# Microcontroller.net
KiCad netlist of a schematic drawn in Altium Designer
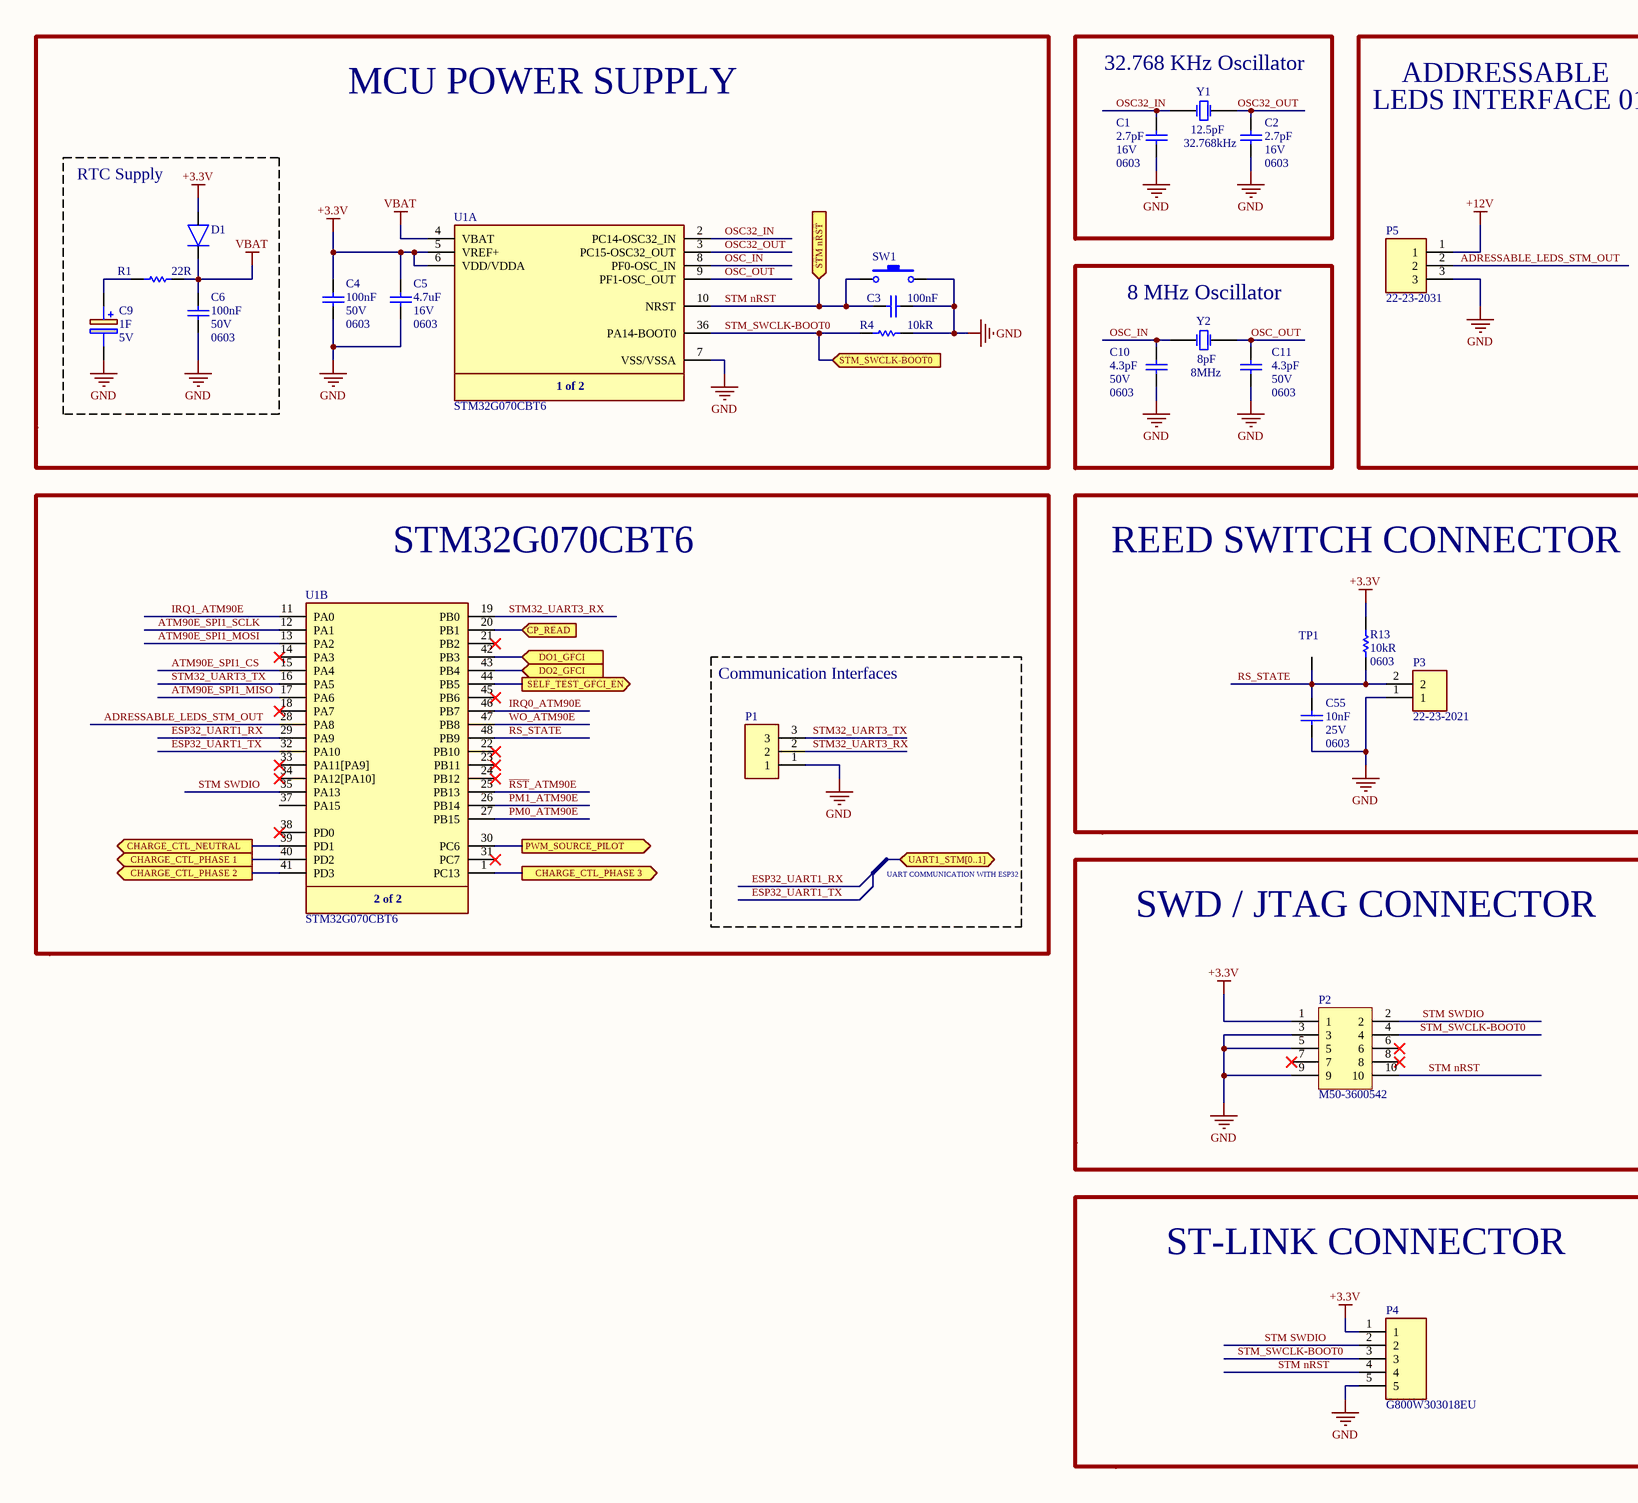
[diagram p0: Microcontroller.SchDoc, left]
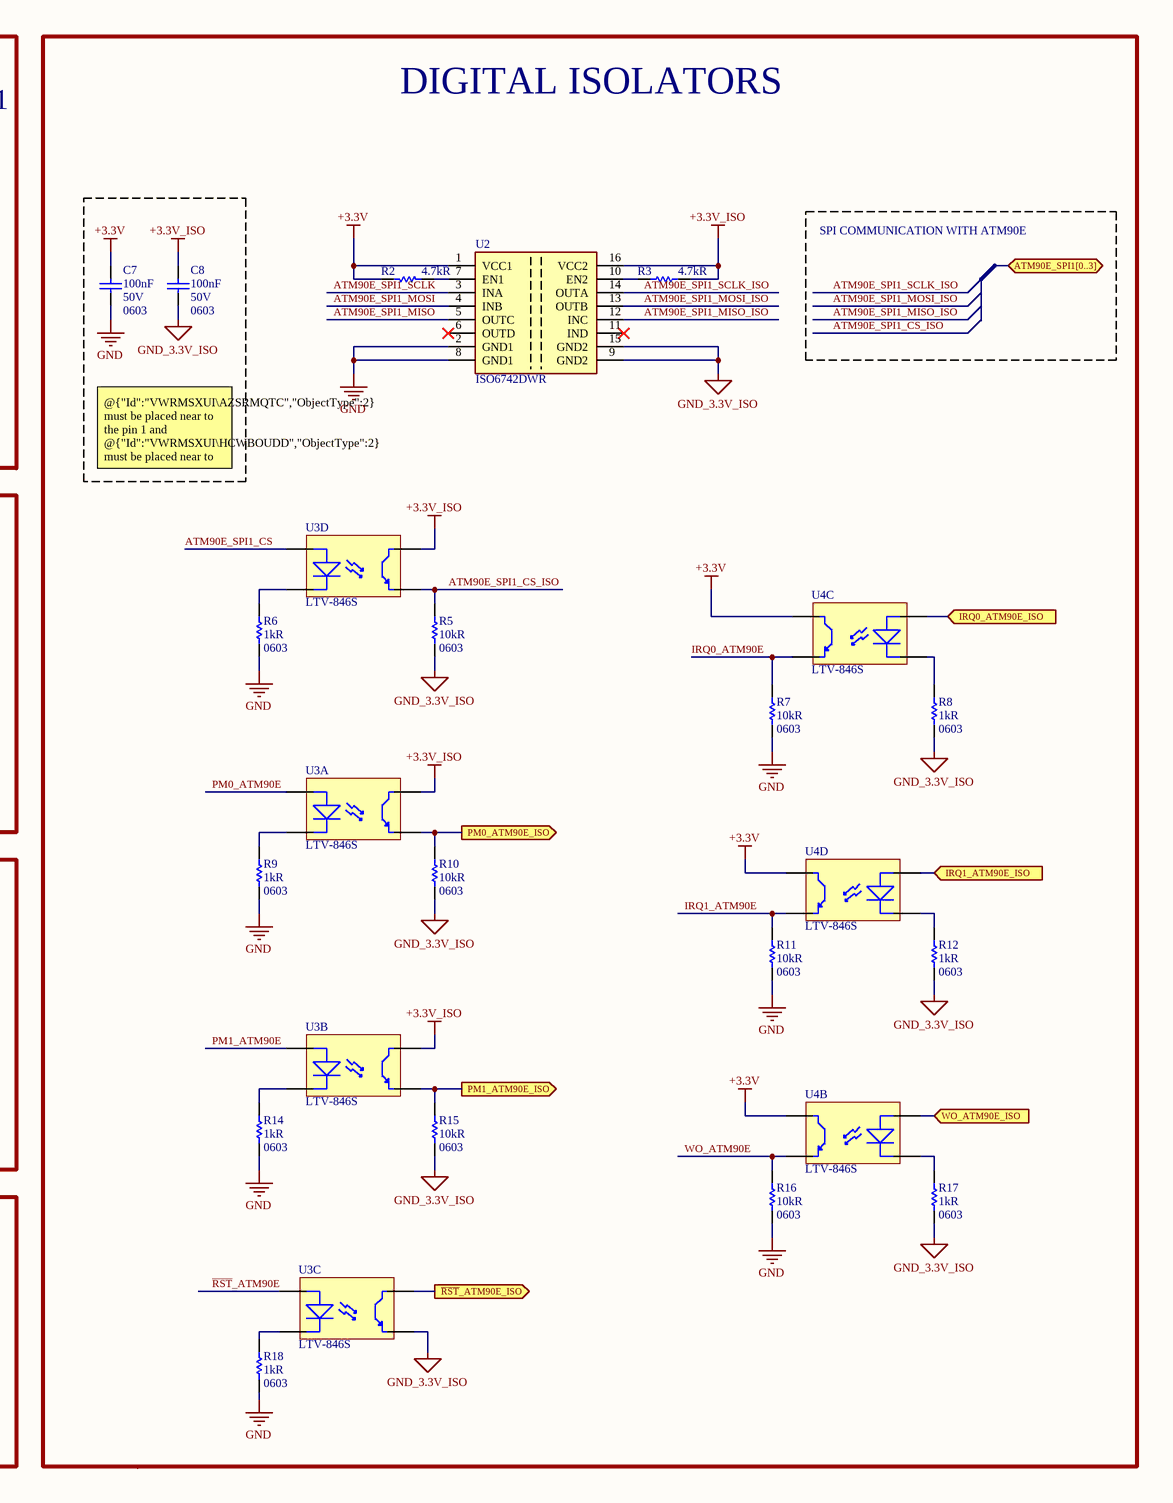
[diagram p1: Microcontroller.SchDoc, right]

(export (version "E")
  (design (tool "Eeschema 10.0.6"))
  (components
    (comp (ref "C1")
      (value "VJ0603A2R7DXJPW1BC")
      (footprint "C0603")
      (description "Multilayer Ceramic Capacitors MLCC - SMD/SMT 0603 2.7pF 16volts C0G +/-0.5pF")
      (fields
        (field (name "MANUFACTURER") "Vishay Vitramon")
        (field (name "VOLTAGE RATING (DC)") "16V")
        (field (name "CASE CODE (IMPERIAL)") "0603")
        (field (name "CAPACITANCE") "2.7pF")
      )
      (libsource (lib "Power2Go - REV05") (part "C_0603_2.7pF_±0.5pF_16V"))
    )
    (comp (ref "C2")
      (value "VJ0603A2R7DXJPW1BC")
      (footprint "C0603")
      (description "Multilayer Ceramic Capacitors MLCC - SMD/SMT 0603 2.7pF 16volts C0G +/-0.5pF")
      (fields
        (field (name "MANUFACTURER") "Vishay Vitramon")
        (field (name "VOLTAGE RATING (DC)") "16V")
        (field (name "CASE CODE (IMPERIAL)") "0603")
        (field (name "CAPACITANCE") "2.7pF")
      )
      (libsource (lib "Power2Go - REV05") (part "C_0603_2.7pF_±0.5pF_16V"))
    )
    (comp (ref "C3")
      (value "100nF")
      (footprint "C0603")
      (description "Cap Ceramic 50V 20% +Tol 20% -Tol X7R 15% TC 0.1uF SMD 0603")
      (fields
        (field (name "MANUFACTURER") "Yageo")
        (field (name "MANUFACTURER PART NUMBER") "CC0603MRX7R9BB104")
      )
      (libsource (lib "Power2Go - REV05") (part "C_0603_0.1uF_50V_20%"))
    )
    (comp (ref "C4")
      (value "100nF")
      (footprint "C0603")
      (description "Cap Ceramic 50V 20% +Tol 20% -Tol X7R 15% TC 0.1uF SMD 0603")
      (fields
        (field (name "MANUFACTURER") "Yageo")
        (field (name "MANUFACTURER PART NUMBER") "CC0603MRX7R9BB104")
        (field (name "CASE/PACKAGE") "0603")
        (field (name "VOLTAGE RATING") "50V")
      )
      (libsource (lib "Power2Go - REV05") (part "C_0603_0.1uF_50V_20%"))
    )
    (comp (ref "C5")
      (value "4.7uF")
      (footprint "C0603")
      (description "CAP CER 4.7UF 16V X5R 0603")
      (fields
        (field (name "MANUFACTURER") "Samsung")
        (field (name "MANUFACTURER PART NUMBER") "CL10A475KO8NNNC")
        (field (name "CASE CODE (IMPERIAL)") "0603")
        (field (name "VOLTAGE RATING") "16V")
      )
      (libsource (lib "Power2Go - REV05") (part "C_0603_4.7uF_16V_10%"))
    )
    (comp (ref "C6")
      (value "100nF")
      (footprint "C0603")
      (description "Cap Ceramic 50V 20% +Tol 20% -Tol X7R 15% TC 0.1uF SMD 0603")
      (fields
        (field (name "MANUFACTURER") "Yageo")
        (field (name "MANUFACTURER PART NUMBER") "CC0603MRX7R9BB104")
        (field (name "CASE/PACKAGE") "0603")
        (field (name "VOLTAGE RATING") "50V")
      )
      (libsource (lib "Power2Go - REV05") (part "C_0603_0.1uF_50V_20%"))
    )
    (comp (ref "C7")
      (value "100nF")
      (footprint "C0603")
      (description "Cap Ceramic 50V 20% +Tol 20% -Tol X7R 15% TC 0.1uF SMD 0603")
      (fields
        (field (name "MANUFACTURER") "Yageo")
        (field (name "MANUFACTURER PART NUMBER") "CC0603MRX7R9BB104")
        (field (name "CASE/PACKAGE") "0603")
        (field (name "VOLTAGE RATING") "50V")
      )
      (libsource (lib "Power2Go - REV05") (part "C_0603_0.1uF_50V_20%"))
    )
    (comp (ref "C8")
      (value "100nF")
      (footprint "C0603")
      (description "Cap Ceramic 50V 20% +Tol 20% -Tol X7R 15% TC 0.1uF SMD 0603")
      (fields
        (field (name "MANUFACTURER") "Yageo")
        (field (name "MANUFACTURER PART NUMBER") "CC0603MRX7R9BB104")
        (field (name "CASE/PACKAGE") "0603")
        (field (name "VOLTAGE RATING") "50V")
      )
      (libsource (lib "Power2Go - REV05") (part "C_0603_0.1uF_50V_20%"))
    )
    (comp (ref "C9")
      (value "1F")
      (footprint "CAP 8MMX18MM")
      (description "Cap 1F 5V 0% to 100% (16 X 8 X 18mm) Radial 11.5mm 65°C Bulk")
      (fields
        (field (name "MANUFACTURER") "Kyocera AVX")
        (field (name "MANUFACTURER PART NUMBER") "SCMR18C105PRBA0")
        (field (name "VOLTAGE RATING") "5V")
      )
      (libsource (lib "Power2Go - REV05") (part "C_8mm x 18mm_1F_5V_ 0% / +100%"))
    )
    (comp (ref "C10")
      (value "4.3pF")
      (footprint "C0603")
      (description "Cap Ceramic 4.3pF 50V C0G 0.25pF Pad SMD 0603 125C T/R")
      (fields
        (field (name "MANUFACTURER") "Yageo")
        (field (name "MANUFACTURER PART NUMBER") "CC0603CRNPO9BN4R3")
        (field (name "CASE CODE (IMPERIAL)") "0603")
        (field (name "VOLTAGE RATING") "50V")
      )
      (libsource (lib "Power2Go - REV05") (part "C_0603_4.3pF_±0.25pF_50V"))
    )
    (comp (ref "C11")
      (value "4.3pF")
      (footprint "C0603")
      (description "Cap Ceramic 4.3pF 50V C0G 0.25pF Pad SMD 0603 125C T/R")
      (fields
        (field (name "MANUFACTURER") "Yageo")
        (field (name "MANUFACTURER PART NUMBER") "CC0603CRNPO9BN4R3")
        (field (name "CASE CODE (IMPERIAL)") "0603")
        (field (name "VOLTAGE RATING") "50V")
      )
      (libsource (lib "Power2Go - REV05") (part "C_0603_4.3pF_±0.25pF_50V"))
    )
    (comp (ref "C55")
      (value "C_0603_0.01uF_25V_10%")
      (footprint "C0603")
      (description "Surface Mount Ceramic Multilayer Capacitor 0.01uF 10% X7R 25V 0603 Paper T/R")
      (fields
        (field (name "MANUFACTURER") "Yageo")
        (field (name "MANUFACTURER PART NUMBER") "CC0603KRX7R8BB103")
        (field (name "VOLTAGE RATING") "25V")
        (field (name "CAPACITANCE") "10nF")
        (field (name "CASE CODE (IMPERIAL)") "0603")
      )
      (libsource (lib "Power2Go - REV05") (part "C_0603_0.01uF_25V_10%"))
    )
    (comp (ref "D1")
      (value "1N4448W-TP")
      (footprint "SOD123")
      (description "Rectifier Diode Switching 100V 0.25A 4ns 2-Pin SOD-123 T/R")
      (fields (field (name "MANUFACTURER") "MCC"))
      (libsource (lib "Power2Go - REV05") (part "D_General_1N4448W-TP"))
    )
    (comp (ref "P1")
      (value "10129378-903001BLF")
      (footprint "HEADER_2.54MM_3POS_PTH")
      (description "Headers & Wire Housings 2.54MM VT ECONOSTIK HDR")
      (fields (field (name "MANUFACTURER") "AMPHENOL ICC (FCI)"))
      (libsource (lib "Power2Go - REV05") (part "P_HEADER_3POS_2.54MM_PTH"))
    )
    (comp (ref "P2")
      (value "M50-3600542")
      (footprint "HEADER_10POS_1.27MM_SMT")
      (description "Headers & Wire Housings 5+5 DIL PIN HDR SMT Au/Sn")
      (fields (field (name "MANUFACTURER") "Harwin") (field (name "MANUFACTURER PART NUMBER") "M50-3600542"))
      (libsource (lib "Power2Go - REV05") (part "P_Harwin_HEADER_10POS_1.27MM_SMT"))
    )
    (comp (ref "P3")
      (value "22-23-2021")
      (footprint "HEADER_KK_2.54MM_2POS")
      (description "KK 254 Solid Header, Vertical, with Friction Lock, 2 Circuits, Tin (Sn) Plating")
      (fields (field (name "MANUFACTURER") "Molex") (field (name "MANUFACTURER PART NUMBER") "22-23-2021"))
      (libsource (lib "Power2Go - REV05") (part "P_Molex_HEADER_2POS_2.54MM_PTH"))
    )
    (comp (ref "P4")
      (value "G800W303018EU")
      (footprint "HEADER_2.54MM_5POS")
      (description "Board to Board Connector Straight Header Single Row 5 Position 2.54mm Pitch Through Hole Bag")
      (fields
        (field (name "MANUFACTURER") "Amphenol")
        (field (name "SUPPLIER PART NUMBER 1") "G800W303018EU")
      )
      (libsource (lib "Power2Go - REV05") (part "P_Header_5POS_2.54MM_PTH"))
    )
    (comp (ref "P5")
      (value "22-23-2031")
      (footprint "HEADER_2.54MM_3POS")
      (description "KK 254 Solid Header, Vertical, with Friction Lock, 3 Circuits, Tin (Sn) Plating, Bag")
      (fields (field (name "MANUFACTURER") "Molex") (field (name "MANUFACTURER PART NUMBER") "22-23-2031"))
      (libsource (lib "Power2Go - REV05") (part "P_Molex_HEADER_3POS_2.54MM_PTH"))
    )
    (comp (ref "R1")
      (value "CRCW060322R0FKEAC")
      (footprint "R0603")
      (description "Thick Film Resistors - SMD 1/10Watt 22ohms 1% Commercial Use")
      (fields
        (field (name "MANUFACTURER") "Vishay")
        (field (name "TOLERANCE") "1%")
        (field (name "RESISTANCE") "22R")
      )
      (libsource (lib "Power2Go - REV05") (part "R_0603_22R_1%_1/10W"))
    )
    (comp (ref "R2")
      (value "R_0603_4.7k_1%_1/10W")
      (footprint "R0603")
      (description "Res Thick Film 0603 4.7K Ohm 1% 0.1W(1/10W) ±100ppm/C Pad SMD T/R")
      (fields
        (field (name "TOLERANCE") "1%")
        (field (name "MANUFACTURER") "Mitsubishi Kamaya")
        (field (name "RESISTANCE") "4.7kR")
      )
      (libsource (lib "Power2Go - REV05") (part "R_0603_4.7k_1%_1/10W"))
    )
    (comp (ref "R3")
      (value "R_0603_4.7k_1%_1/10W")
      (footprint "R0603")
      (description "Res Thick Film 0603 4.7K Ohm 1% 0.1W(1/10W) ±100ppm/C Pad SMD T/R")
      (fields
        (field (name "TOLERANCE") "1%")
        (field (name "MANUFACTURER") "Mitsubishi Kamaya")
        (field (name "RESISTANCE") "4.7kR")
      )
      (libsource (lib "Power2Go - REV05") (part "R_0603_4.7k_1%_1/10W"))
    )
    (comp (ref "R4")
      (value "10kR")
      (footprint "R0603")
      (fields
        (field (name "MANUFACTURER") "Vishay")
        (field (name "MANUFACTURER PART NUMBER") "CRCW060310K0JNEBC")
        (field (name "TOLERANCE") "5%")
      )
      (libsource (lib "Power2Go - REV05") (part "R_0603_10kR_5%_1/10W"))
    )
    (comp (ref "R5")
      (value "10kR")
      (footprint "R0603")
      (fields
        (field (name "MANUFACTURER") "Vishay")
        (field (name "MANUFACTURER PART NUMBER") "CRCW060310K0JNEBC")
        (field (name "TOLERANCE") "5%")
        (field (name "CASE/PACKAGE") "0603")
      )
      (libsource (lib "Power2Go - REV05") (part "R_0603_10kR_5%_1/10W"))
    )
    (comp (ref "R6")
      (value "R_0603_1kR_1%_1/10W")
      (footprint "R0603")
      (description "Res Thick Film 0603 1K Ohm 1% 1/10W ±100ppm/°C Molded SMD Paper T/R")
      (fields
        (field (name "MANUFACTURER") "Vishay")
        (field (name "MANUFACTURER PART NUMBER") "CRCW06031K00FKEAC")
        (field (name "SIZE CODE") "0603")
        (field (name "RESISTANCE") "1kR")
      )
      (libsource (lib "Power2Go - REV05") (part "R_0603_1kR_1%_1/10W"))
    )
    (comp (ref "R7")
      (value "10kR")
      (footprint "R0603")
      (fields
        (field (name "MANUFACTURER") "Vishay")
        (field (name "MANUFACTURER PART NUMBER") "CRCW060310K0JNEBC")
        (field (name "TOLERANCE") "5%")
        (field (name "CASE/PACKAGE") "0603")
      )
      (libsource (lib "Power2Go - REV05") (part "R_0603_10kR_5%_1/10W"))
    )
    (comp (ref "R8")
      (value "R_0603_1kR_1%_1/10W")
      (footprint "R0603")
      (description "Res Thick Film 0603 1K Ohm 1% 1/10W ±100ppm/°C Molded SMD Paper T/R")
      (fields
        (field (name "MANUFACTURER") "Vishay")
        (field (name "MANUFACTURER PART NUMBER") "CRCW06031K00FKEAC")
        (field (name "SIZE CODE") "0603")
        (field (name "RESISTANCE") "1kR")
      )
      (libsource (lib "Power2Go - REV05") (part "R_0603_1kR_1%_1/10W"))
    )
    (comp (ref "R9")
      (value "R_0603_1kR_1%_1/10W")
      (footprint "R0603")
      (description "Res Thick Film 0603 1K Ohm 1% 1/10W ±100ppm/°C Molded SMD Paper T/R")
      (fields
        (field (name "MANUFACTURER") "Vishay")
        (field (name "MANUFACTURER PART NUMBER") "CRCW06031K00FKEAC")
        (field (name "SIZE CODE") "0603")
        (field (name "RESISTANCE") "1kR")
      )
      (libsource (lib "Power2Go - REV05") (part "R_0603_1kR_1%_1/10W"))
    )
    (comp (ref "R10")
      (value "10kR")
      (footprint "R0603")
      (fields
        (field (name "MANUFACTURER") "Vishay")
        (field (name "MANUFACTURER PART NUMBER") "CRCW060310K0JNEBC")
        (field (name "TOLERANCE") "5%")
        (field (name "CASE/PACKAGE") "0603")
      )
      (libsource (lib "Power2Go - REV05") (part "R_0603_10kR_5%_1/10W"))
    )
    (comp (ref "R11")
      (value "10kR")
      (footprint "R0603")
      (fields
        (field (name "MANUFACTURER") "Vishay")
        (field (name "MANUFACTURER PART NUMBER") "CRCW060310K0JNEBC")
        (field (name "TOLERANCE") "5%")
        (field (name "CASE/PACKAGE") "0603")
      )
      (libsource (lib "Power2Go - REV05") (part "R_0603_10kR_5%_1/10W"))
    )
    (comp (ref "R12")
      (value "R_0603_1kR_1%_1/10W")
      (footprint "R0603")
      (description "Res Thick Film 0603 1K Ohm 1% 1/10W ±100ppm/°C Molded SMD Paper T/R")
      (fields
        (field (name "MANUFACTURER") "Vishay")
        (field (name "MANUFACTURER PART NUMBER") "CRCW06031K00FKEAC")
        (field (name "SIZE CODE") "0603")
        (field (name "RESISTANCE") "1kR")
      )
      (libsource (lib "Power2Go - REV05") (part "R_0603_1kR_1%_1/10W"))
    )
    (comp (ref "R13")
      (value "10kR")
      (footprint "R0603")
      (fields
        (field (name "MANUFACTURER") "Vishay")
        (field (name "MANUFACTURER PART NUMBER") "CRCW060310K0JNEBC")
        (field (name "TOLERANCE") "5%")
        (field (name "CASE/PACKAGE") "0603")
      )
      (libsource (lib "Power2Go - REV05") (part "R_0603_10kR_5%_1/10W"))
    )
    (comp (ref "R14")
      (value "R_0603_1kR_1%_1/10W")
      (footprint "R0603")
      (description "Res Thick Film 0603 1K Ohm 1% 1/10W ±100ppm/°C Molded SMD Paper T/R")
      (fields
        (field (name "MANUFACTURER") "Vishay")
        (field (name "MANUFACTURER PART NUMBER") "CRCW06031K00FKEAC")
        (field (name "SIZE CODE") "0603")
        (field (name "RESISTANCE") "1kR")
      )
      (libsource (lib "Power2Go - REV05") (part "R_0603_1kR_1%_1/10W"))
    )
    (comp (ref "R15")
      (value "10kR")
      (footprint "R0603")
      (fields
        (field (name "MANUFACTURER") "Vishay")
        (field (name "MANUFACTURER PART NUMBER") "CRCW060310K0JNEBC")
        (field (name "TOLERANCE") "5%")
        (field (name "CASE/PACKAGE") "0603")
      )
      (libsource (lib "Power2Go - REV05") (part "R_0603_10kR_5%_1/10W"))
    )
    (comp (ref "R16")
      (value "10kR")
      (footprint "R0603")
      (fields
        (field (name "MANUFACTURER") "Vishay")
        (field (name "MANUFACTURER PART NUMBER") "CRCW060310K0JNEBC")
        (field (name "TOLERANCE") "5%")
        (field (name "CASE/PACKAGE") "0603")
      )
      (libsource (lib "Power2Go - REV05") (part "R_0603_10kR_5%_1/10W"))
    )
    (comp (ref "R17")
      (value "R_0603_1kR_1%_1/10W")
      (footprint "R0603")
      (description "Res Thick Film 0603 1K Ohm 1% 1/10W ±100ppm/°C Molded SMD Paper T/R")
      (fields
        (field (name "MANUFACTURER") "Vishay")
        (field (name "MANUFACTURER PART NUMBER") "CRCW06031K00FKEAC")
        (field (name "SIZE CODE") "0603")
        (field (name "RESISTANCE") "1kR")
      )
      (libsource (lib "Power2Go - REV05") (part "R_0603_1kR_1%_1/10W"))
    )
    (comp (ref "R18")
      (value "R_0603_1kR_1%_1/10W")
      (footprint "R0603")
      (description "Res Thick Film 0603 1K Ohm 1% 1/10W ±100ppm/°C Molded SMD Paper T/R")
      (fields
        (field (name "MANUFACTURER") "Vishay")
        (field (name "MANUFACTURER PART NUMBER") "CRCW06031K00FKEAC")
        (field (name "SIZE CODE") "0603")
        (field (name "RESISTANCE") "1kR")
      )
      (libsource (lib "Power2Go - REV05") (part "R_0603_1kR_1%_1/10W"))
    )
    (comp (ref "SW1")
      (value "PTS810SJM250SMTRLFS")
      (footprint "PUSH BUTTON 4.2mm x 3.2 mm")
      (description "SWITCHTACTILESPST-NO0.05A16V")
      (fields (field (name "MANUFACTURER") "ITT C&K"))
      (libsource (lib "Power2Go - REV05") (part "B_PushButton_PTS810SJM250SMTRLFS"))
    )
    (comp (ref "TP1")
      (value "S2761-46R")
      (footprint "TP_S276146R")
      (fields (field (name "MANUFACTURER") "Harwin"))
      (libsource (lib "Power2Go - REV05") (part "TP_S2761-46R_SMT"))
    )
    (comp (ref "U1")
      (value "STM32G070CBT6")
      (footprint "LQFP-48")
      (description "MCU 32-Bit ARM Cortex-M0+ RISC 128KB Flash 2V to 3.6V 48-Pin LQFP Tray")
      (fields
        (field (name "MANUFACTURER") "STMicroelectronics")
        (field (name "MANUFACTURER PART NUMBER") "STM32G070CBT6")
      )
      (libsource (lib "Power2Go - REV05") (part "U_STM32G070CBT6_LQFP-48"))
    )
    (comp (ref "U2")
      (value "ISO6742DWR")
      (footprint "SOIC-16")
      (description "General-purpose, quad-channel, 2/2 digital isolator 16-SOIC -40 to 125")
      (fields
        (field (name "MANUFACTURER") "Texas Instruments")
        (field (name "MANUFACTURER PART NUMBER") "ISO6742DWR")
      )
      (libsource (lib "Power2Go - REV05") (part "U_ISO6742DWR _SOIC-16"))
    )
    (comp (ref "U3")
      (value "LTV-846S")
      (footprint "PDIP-16")
      (description "LTV Series Quad Channel 80 V 5000 Vrms Transistor Output Optocoupler SMT -DIP-16")
      (fields
        (field (name "MANUFACTURER") "Vishay Lite-On")
        (field (name "MANUFACTURER PART NUMBER") "LTV-846S")
      )
      (libsource (lib "") (part "U_LTV-846S_PDIP-16_1"))
    )
    (comp (ref "U4")
      (value "LTV-846S")
      (footprint "PDIP-16")
      (description "LTV Series Quad Channel 80 V 5000 Vrms Transistor Output Optocoupler SMT -DIP-16")
      (fields
        (field (name "MANUFACTURER") "Vishay Lite-On")
        (field (name "MANUFACTURER PART NUMBER") "LTV-846S")
      )
      (libsource (lib "Power2Go - REV05") (part "U_LTV-846S_PDIP-16"))
    )
    (comp (ref "Y1")
      (value "FK135EIHM0.032768-T3")
      (footprint "Y32.768KHz")
      (description "Crystal 0.032768MHz ±20ppm (Tol) 12.5pF Flexural 70000Ohm 2-Pin SMD T/R")
      (fields
        (field (name "MANUFACTURER") "Fox Electronics")
        (field (name "LOAD CAPACITANCE") "12.5pF")
        (field (name "FREQUENCY") "32.768kHz")
      )
      (libsource (lib "Power2Go - REV05") (part "Y_32.768KHz_FK135EIHM0.032768-T3"))
    )
    (comp (ref "Y2")
      (value "NX5032GA-8.000M-STD-CSU-1")
      (footprint "Y8MHz")
      (description "Crystal 8MHz +/-50ppm (Tol) +/-150ppm (Stability) 8pF FUND 300Ohm Automotive 2-Pin SMD")
      (fields
        (field (name "MANUFACTURER") "NDK")
        (field (name "FREQUENCY") "8MHz")
        (field (name "LOAD CAPACITANCE") "8pF")
      )
      (libsource (lib "Power2Go - REV05") (part "Y_8MHz_NX5032GA-8.000M-STD-CSU-1"))
    )
  )
  (nets
    (net (code "7") (name "+3.3V") (class "Default")
      (node (ref "C4") (pin "2") (pinfunction "2_2") (pintype "passive"))
      (node (ref "C5") (pin "2") (pinfunction "2_2") (pintype "passive"))
      (node (ref "C7") (pin "1") (pinfunction "1_1") (pintype "passive"))
      (node (ref "D1") (pin "2") (pinfunction "A_2") (pintype "passive"))
      (node (ref "P2") (pin "1") (pinfunction "1_1") (pintype "passive"))
      (node (ref "P4") (pin "1") (pinfunction "1_1") (pintype "passive"))
      (node (ref "R13") (pin "2") (pinfunction "2_2") (pintype "passive"))
      (node (ref "R2") (pin "2") (pinfunction "2_2") (pintype "passive"))
      (node (ref "U1") (pin "5") (pinfunction "VREF+_5") (pintype "passive"))
      (node (ref "U1") (pin "6") (pinfunction "VDD/VDDA_6") (pintype "passive"))
      (node (ref "U2") (pin "1") (pinfunction "VCC1_1") (pintype "passive"))
      (node (ref "U4") (pin "10") (pinfunction "C4_10") (pintype "passive"))
      (node (ref "U4") (pin "12") (pinfunction "C3_12") (pintype "passive"))
      (node (ref "U4") (pin "14") (pinfunction "C2_14") (pintype "passive"))
    )
    (net (code "8") (name "+3.3V_ISO") (class "Default")
      (node (ref "C8") (pin "1") (pinfunction "1_1") (pintype "passive"))
      (node (ref "R3") (pin "2") (pinfunction "2_2") (pintype "passive"))
      (node (ref "U2") (pin "16") (pinfunction "VCC2_16") (pintype "passive"))
      (node (ref "U3") (pin "10") (pinfunction "C4_10") (pintype "passive"))
      (node (ref "U3") (pin "14") (pinfunction "C2_14") (pintype "passive"))
      (node (ref "U3") (pin "16") (pinfunction "C1_16") (pintype "passive"))
    )
    (net (code "9") (name "+12V") (class "Default")
      (node (ref "P5") (pin "1") (pinfunction "1_1") (pintype "passive"))
    )
    (net (code "10") (name "/ADRESSABLE_LEDS_STM_OUT") (class "Default")
      (node (ref "P5") (pin "2") (pinfunction "2_2") (pintype "passive"))
      (node (ref "U1") (pin "28") (pinfunction "PA8_28") (pintype "passive"))
    )
    (net (code "12") (name "/ATM90E_SPI1_CS") (class "Default")
      (node (ref "U1") (pin "15") (pinfunction "PA4_15") (pintype "passive"))
      (node (ref "U3") (pin "7") (pinfunction "A4_7") (pintype "passive"))
    )
    (net (code "13") (name "/ATM90E_SPI1_CS_ISO") (class "Default")
      (node (ref "R5") (pin "2") (pinfunction "2_2") (pintype "passive"))
      (node (ref "U3") (pin "9") (pinfunction "E4_9") (pintype "passive"))
    )
    (net (code "14") (name "/ATM90E_SPI1_MISO") (class "Default")
      (node (ref "U1") (pin "17") (pinfunction "PA6_17") (pintype "passive"))
      (node (ref "U2") (pin "5") (pinfunction "OUTC_5") (pintype "passive"))
    )
    (net (code "15") (name "/ATM90E_SPI1_MISO_ISO") (class "Default")
      (node (ref "U2") (pin "12") (pinfunction "INC_12") (pintype "passive"))
    )
    (net (code "16") (name "/ATM90E_SPI1_MOSI") (class "Default")
      (node (ref "U1") (pin "13") (pinfunction "PA2_13") (pintype "passive"))
      (node (ref "U2") (pin "4") (pinfunction "INB_4") (pintype "passive"))
    )
    (net (code "17") (name "/ATM90E_SPI1_MOSI_ISO") (class "Default")
      (node (ref "U2") (pin "13") (pinfunction "OUTB_13") (pintype "passive"))
    )
    (net (code "18") (name "/ATM90E_SPI1_SCLK") (class "Default")
      (node (ref "U1") (pin "12") (pinfunction "PA1_12") (pintype "passive"))
      (node (ref "U2") (pin "3") (pinfunction "INA_3") (pintype "passive"))
    )
    (net (code "19") (name "/ATM90E_SPI1_SCLK_ISO") (class "Default")
      (node (ref "U2") (pin "14") (pinfunction "OUTA_14") (pintype "passive"))
    )
    (net (code "20") (name "/CHARGE_CTL_NEUTRAL") (class "Default")
      (node (ref "U1") (pin "39") (pinfunction "PD1_39") (pintype "passive"))
    )
    (net (code "21") (name "/CHARGE_CTL_PHASE 1") (class "Default")
      (node (ref "U1") (pin "40") (pinfunction "PD2_40") (pintype "passive"))
    )
    (net (code "22") (name "/CHARGE_CTL_PHASE 2") (class "Default")
      (node (ref "U1") (pin "41") (pinfunction "PD3_41") (pintype "passive"))
    )
    (net (code "23") (name "/CHARGE_CTL_PHASE 3") (class "Default")
      (node (ref "U1") (pin "1") (pinfunction "PC13_1") (pintype "passive"))
    )
    (net (code "24") (name "/CP_READ") (class "Default")
      (node (ref "U1") (pin "20") (pinfunction "PB1_20") (pintype "passive"))
    )
    (net (code "25") (name "/DO1_GFCI") (class "Default")
      (node (ref "U1") (pin "42") (pinfunction "PB3_42") (pintype "passive"))
    )
    (net (code "26") (name "/DO2_GFCI") (class "Default")
      (node (ref "U1") (pin "43") (pinfunction "PB4_43") (pintype "passive"))
    )
    (net (code "27") (name "/ESP32_UART1_RX") (class "Default")
      (node (ref "U1") (pin "29") (pinfunction "PA9_29") (pintype "passive"))
    )
    (net (code "28") (name "/ESP32_UART1_TX") (class "Default")
      (node (ref "U1") (pin "32") (pinfunction "PA10_32") (pintype "passive"))
    )
    (net (code "29") (name "/IRQ0_ATM90E") (class "Default")
      (node (ref "R7") (pin "2") (pinfunction "2_2") (pintype "passive"))
      (node (ref "U1") (pin "46") (pinfunction "PB7_46") (pintype "passive"))
      (node (ref "U4") (pin "11") (pinfunction "E3_11") (pintype "passive"))
    )
    (net (code "30") (name "/IRQ0_ATM90E_ISO") (class "Default")
      (node (ref "U4") (pin "5") (pinfunction "A3_5") (pintype "passive"))
    )
    (net (code "31") (name "/IRQ1_ATM90E") (class "Default")
      (node (ref "R11") (pin "2") (pinfunction "2_2") (pintype "passive"))
      (node (ref "U1") (pin "11") (pinfunction "PA0_11") (pintype "passive"))
      (node (ref "U4") (pin "9") (pinfunction "E4_9") (pintype "passive"))
    )
    (net (code "32") (name "/IRQ1_ATM90E_ISO") (class "Default")
      (node (ref "U4") (pin "7") (pinfunction "A4_7") (pintype "passive"))
    )
    (net (code "33") (name "/OSC32_IN") (class "Default")
      (node (ref "C1") (pin "2") (pinfunction "2_2") (pintype "passive"))
      (node (ref "U1") (pin "2") (pinfunction "PC14-OSC32_IN_2") (pintype "passive"))
      (node (ref "Y1") (pin "2") (pinfunction "OSC2_2") (pintype "passive"))
    )
    (net (code "34") (name "/OSC32_OUT") (class "Default")
      (node (ref "C2") (pin "2") (pinfunction "2_2") (pintype "passive"))
      (node (ref "U1") (pin "3") (pinfunction "PC15-OSC32_OUT_3") (pintype "passive"))
      (node (ref "Y1") (pin "1") (pinfunction "OSC1_1") (pintype "passive"))
    )
    (net (code "35") (name "/OSC_IN") (class "Default")
      (node (ref "C10") (pin "2") (pinfunction "2_2") (pintype "passive"))
      (node (ref "U1") (pin "8") (pinfunction "PF0-OSC_IN_8") (pintype "passive"))
      (node (ref "Y2") (pin "2") (pinfunction "OSC2_2") (pintype "passive"))
    )
    (net (code "36") (name "/OSC_OUT") (class "Default")
      (node (ref "C11") (pin "2") (pinfunction "2_2") (pintype "passive"))
      (node (ref "U1") (pin "9") (pinfunction "PF1-OSC_OUT_9") (pintype "passive"))
      (node (ref "Y2") (pin "1") (pinfunction "OSC1_1") (pintype "passive"))
    )
    (net (code "37") (name "/PM0_ATM90E") (class "Default")
      (node (ref "U1") (pin "27") (pinfunction "PB15_27") (pintype "passive"))
      (node (ref "U3") (pin "1") (pinfunction "A1_1") (pintype "passive"))
    )
    (net (code "38") (name "/PM0_ATM90E_ISO") (class "Default")
      (node (ref "R10") (pin "2") (pinfunction "2_2") (pintype "passive"))
      (node (ref "U3") (pin "15") (pinfunction "E1_15") (pintype "passive"))
    )
    (net (code "39") (name "/PM1_ATM90E") (class "Default")
      (node (ref "U1") (pin "26") (pinfunction "PB14_26") (pintype "passive"))
      (node (ref "U3") (pin "3") (pinfunction "A2_3") (pintype "passive"))
    )
    (net (code "40") (name "/PM1_ATM90E_ISO") (class "Default")
      (node (ref "R15") (pin "2") (pinfunction "2_2") (pintype "passive"))
      (node (ref "U3") (pin "13") (pinfunction "E2_13") (pintype "passive"))
    )
    (net (code "41") (name "/PWM_SOURCE_PILOT") (class "Default")
      (node (ref "U1") (pin "30") (pinfunction "PC6_30") (pintype "passive"))
    )
    (net (code "42") (name "/RS_STATE") (class "Default")
      (node (ref "C55") (pin "2") (pinfunction "2_2") (pintype "passive"))
      (node (ref "P3") (pin "2") (pinfunction "2_2") (pintype "passive"))
      (node (ref "R13") (pin "1") (pinfunction "1_1") (pintype "passive"))
      (node (ref "TP1") (pin "1") (pinfunction "1_1") (pintype "passive"))
      (node (ref "U1") (pin "48") (pinfunction "PB9_48") (pintype "passive"))
    )
    (net (code "43") (name "/SELF_TEST_GFCI_EN") (class "Default")
      (node (ref "U1") (pin "44") (pinfunction "PB5_44") (pintype "passive"))
    )
    (net (code "44") (name "/STM SWDIO") (class "Default")
      (node (ref "P2") (pin "2") (pinfunction "2_2") (pintype "passive"))
      (node (ref "P4") (pin "2") (pinfunction "2_2") (pintype "passive"))
      (node (ref "U1") (pin "35") (pinfunction "PA13_35") (pintype "passive"))
    )
    (net (code "45") (name "/STM nRST") (class "Default")
      (node (ref "C3") (pin "1") (pinfunction "1_1") (pintype "passive"))
      (node (ref "P2") (pin "10") (pinfunction "10_10") (pintype "passive"))
      (node (ref "P4") (pin "4") (pinfunction "4_4") (pintype "passive"))
      (node (ref "SW1") (pin "1") (pinfunction "1_1") (pintype "passive"))
      (node (ref "U1") (pin "10") (pinfunction "NRST_10") (pintype "passive"))
    )
    (net (code "46") (name "/STM32_UART3_RX") (class "Default")
      (node (ref "P1") (pin "2") (pinfunction "2_2") (pintype "passive"))
      (node (ref "U1") (pin "19") (pinfunction "PB0_19") (pintype "passive"))
    )
    (net (code "47") (name "/STM32_UART3_TX") (class "Default")
      (node (ref "P1") (pin "3") (pinfunction "3_3") (pintype "passive"))
      (node (ref "U1") (pin "16") (pinfunction "PA5_16") (pintype "passive"))
    )
    (net (code "48") (name "/STM_SWCLK-BOOT0") (class "Default")
      (node (ref "P2") (pin "4") (pinfunction "4_4") (pintype "passive"))
      (node (ref "P4") (pin "3") (pinfunction "3_3") (pintype "passive"))
      (node (ref "R4") (pin "1") (pinfunction "1_1") (pintype "passive"))
      (node (ref "U1") (pin "36") (pinfunction "PA14-BOOT0_36") (pintype "passive"))
    )
    (net (code "50") (name "/WO_ATM90E") (class "Default")
      (node (ref "R16") (pin "2") (pinfunction "2_2") (pintype "passive"))
      (node (ref "U1") (pin "47") (pinfunction "PB8_47") (pintype "passive"))
      (node (ref "U4") (pin "13") (pinfunction "E2_13") (pintype "passive"))
    )
    (net (code "51") (name "/WO_ATM90E_ISO") (class "Default")
      (node (ref "U4") (pin "3") (pinfunction "A2_3") (pintype "passive"))
    )
    (net (code "52") (name "/~{RST}_ATM90E") (class "Default")
      (node (ref "U1") (pin "25") (pinfunction "PB13_25") (pintype "passive"))
      (node (ref "U3") (pin "5") (pinfunction "A3_5") (pintype "passive"))
    )
    (net (code "53") (name "/~{RST}_ATM90E_ISO") (class "Default")
      (node (ref "U3") (pin "12") (pinfunction "C3_12") (pintype "passive"))
    )
    (net (code "54") (name "GND") (class "Default")
      (node (ref "C1") (pin "1") (pinfunction "1_1") (pintype "passive"))
      (node (ref "C10") (pin "1") (pinfunction "1_1") (pintype "passive"))
      (node (ref "C11") (pin "1") (pinfunction "1_1") (pintype "passive"))
      (node (ref "C2") (pin "1") (pinfunction "1_1") (pintype "passive"))
      (node (ref "C3") (pin "2") (pinfunction "2_2") (pintype "passive"))
      (node (ref "C4") (pin "1") (pinfunction "1_1") (pintype "passive"))
      (node (ref "C5") (pin "1") (pinfunction "1_1") (pintype "passive"))
      (node (ref "C55") (pin "1") (pinfunction "1_1") (pintype "passive"))
      (node (ref "C6") (pin "1") (pinfunction "1_1") (pintype "passive"))
      (node (ref "C7") (pin "2") (pinfunction "2_2") (pintype "passive"))
      (node (ref "C9") (pin "2") (pinfunction "-_2") (pintype "passive"))
      (node (ref "P1") (pin "1") (pinfunction "1_1") (pintype "passive"))
      (node (ref "P2") (pin "3") (pinfunction "3_3") (pintype "passive"))
      (node (ref "P2") (pin "5") (pinfunction "5_5") (pintype "passive"))
      (node (ref "P2") (pin "9") (pinfunction "9_9") (pintype "passive"))
      (node (ref "P3") (pin "1") (pinfunction "1_1") (pintype "passive"))
      (node (ref "P4") (pin "5") (pinfunction "5_5") (pintype "passive"))
      (node (ref "P5") (pin "3") (pinfunction "3_3") (pintype "passive"))
      (node (ref "R11") (pin "1") (pinfunction "1_1") (pintype "passive"))
      (node (ref "R14") (pin "2") (pinfunction "2_2") (pintype "passive"))
      (node (ref "R16") (pin "1") (pinfunction "1_1") (pintype "passive"))
      (node (ref "R18") (pin "2") (pinfunction "2_2") (pintype "passive"))
      (node (ref "R4") (pin "2") (pinfunction "2_2") (pintype "passive"))
      (node (ref "R6") (pin "2") (pinfunction "2_2") (pintype "passive"))
      (node (ref "R7") (pin "1") (pinfunction "1_1") (pintype "passive"))
      (node (ref "R9") (pin "2") (pinfunction "2_2") (pintype "passive"))
      (node (ref "SW1") (pin "3") (pinfunction "3_3") (pintype "passive"))
      (node (ref "U1") (pin "7") (pinfunction "VSS/VSSA_7") (pintype "passive"))
      (node (ref "U2") (pin "2") (pinfunction "GND1_2") (pintype "passive"))
      (node (ref "U2") (pin "8") (pinfunction "GND1_8") (pintype "passive"))
    )
    (net (code "55") (name "GND_3.3V_ISO") (class "Default")
      (node (ref "C8") (pin "2") (pinfunction "2_2") (pintype "passive"))
      (node (ref "R10") (pin "1") (pinfunction "1_1") (pintype "passive"))
      (node (ref "R12") (pin "2") (pinfunction "2_2") (pintype "passive"))
      (node (ref "R15") (pin "1") (pinfunction "1_1") (pintype "passive"))
      (node (ref "R17") (pin "2") (pinfunction "2_2") (pintype "passive"))
      (node (ref "R5") (pin "1") (pinfunction "1_1") (pintype "passive"))
      (node (ref "R8") (pin "2") (pinfunction "2_2") (pintype "passive"))
      (node (ref "U2") (pin "15") (pinfunction "GND2_15") (pintype "passive"))
      (node (ref "U2") (pin "9") (pinfunction "GND2_9") (pintype "passive"))
      (node (ref "U3") (pin "11") (pinfunction "E3_11") (pintype "passive"))
    )
    (net (code "56") (name "Net-(C9-+)") (class "Default")
      (node (ref "C9") (pin "1") (pinfunction "+_1") (pintype "passive"))
      (node (ref "R1") (pin "1") (pinfunction "1_1") (pintype "passive"))
    )
    (net (code "57") (name "Net-(U2-EN1)") (class "Default")
      (node (ref "R2") (pin "1") (pinfunction "1_1") (pintype "passive"))
      (node (ref "U2") (pin "7") (pinfunction "EN1_7") (pintype "passive"))
    )
    (net (code "58") (name "Net-(U2-EN2)") (class "Default")
      (node (ref "R3") (pin "1") (pinfunction "1_1") (pintype "passive"))
      (node (ref "U2") (pin "10") (pinfunction "EN2_10") (pintype "passive"))
    )
    (net (code "59") (name "Net-(U3A-K2)") (class "Default")
      (node (ref "R9") (pin "1") (pinfunction "1_1") (pintype "passive"))
      (node (ref "U3") (pin "2") (pinfunction "K2_2") (pintype "passive"))
    )
    (net (code "60") (name "Net-(U3B-K2)") (class "Default")
      (node (ref "R14") (pin "1") (pinfunction "1_1") (pintype "passive"))
      (node (ref "U3") (pin "4") (pinfunction "K2_4") (pintype "passive"))
    )
    (net (code "61") (name "Net-(U3C-K3)") (class "Default")
      (node (ref "R18") (pin "1") (pinfunction "1_1") (pintype "passive"))
      (node (ref "U3") (pin "6") (pinfunction "K3_6") (pintype "passive"))
    )
    (net (code "62") (name "Net-(U3D-K4)") (class "Default")
      (node (ref "R6") (pin "1") (pinfunction "1_1") (pintype "passive"))
      (node (ref "U3") (pin "8") (pinfunction "K4_8") (pintype "passive"))
    )
    (net (code "63") (name "Net-(U4B-K2)") (class "Default")
      (node (ref "R17") (pin "1") (pinfunction "1_1") (pintype "passive"))
      (node (ref "U4") (pin "4") (pinfunction "K2_4") (pintype "passive"))
    )
    (net (code "64") (name "Net-(U4C-K3)") (class "Default")
      (node (ref "R8") (pin "1") (pinfunction "1_1") (pintype "passive"))
      (node (ref "U4") (pin "6") (pinfunction "K3_6") (pintype "passive"))
    )
    (net (code "65") (name "Net-(U4D-K4)") (class "Default")
      (node (ref "R12") (pin "1") (pinfunction "1_1") (pintype "passive"))
      (node (ref "U4") (pin "8") (pinfunction "K4_8") (pintype "passive"))
    )
    (net (code "66") (name "VBAT") (class "Default")
      (node (ref "C6") (pin "2") (pinfunction "2_2") (pintype "passive"))
      (node (ref "D1") (pin "1") (pinfunction "K_1") (pintype "passive"))
      (node (ref "R1") (pin "2") (pinfunction "2_2") (pintype "passive"))
      (node (ref "U1") (pin "4") (pinfunction "VBAT_4") (pintype "passive"))
    )
    (net (code "67") (name "unconnected-(P2-Pad6)") (class "Default")
      (node (ref "P2") (pin "6") (pinfunction "6_6") (pintype "passive+no_connect"))
    )
    (net (code "68") (name "unconnected-(P2-Pad7)") (class "Default")
      (node (ref "P2") (pin "7") (pinfunction "7_7") (pintype "passive+no_connect"))
    )
    (net (code "69") (name "unconnected-(P2-Pad8)") (class "Default")
      (node (ref "P2") (pin "8") (pinfunction "8_8") (pintype "passive+no_connect"))
    )
    (net (code "70") (name "unconnected-(U1B-PA3-Pad14)") (class "Default")
      (node (ref "U1") (pin "14") (pinfunction "PA3_14") (pintype "passive+no_connect"))
    )
    (net (code "71") (name "unconnected-(U1B-PA7-Pad18)") (class "Default")
      (node (ref "U1") (pin "18") (pinfunction "PA7_18") (pintype "passive+no_connect"))
    )
    (net (code "72") (name "unconnected-(U1B-PA11[PA9]-Pad33)") (class "Default")
      (node (ref "U1") (pin "33") (pinfunction "PA11[PA9]_33") (pintype "passive+no_connect"))
    )
    (net (code "73") (name "unconnected-(U1B-PA12[PA10]-Pad34)") (class "Default")
      (node (ref "U1") (pin "34") (pinfunction "PA12[PA10]_34") (pintype "passive+no_connect"))
    )
    (net (code "74") (name "unconnected-(U1B-PA15-Pad37)") (class "Default")
      (node (ref "U1") (pin "37") (pinfunction "PA15_37") (pintype "passive"))
    )
    (net (code "75") (name "unconnected-(U1B-PB2-Pad21)") (class "Default")
      (node (ref "U1") (pin "21") (pinfunction "PB2_21") (pintype "passive+no_connect"))
    )
    (net (code "76") (name "unconnected-(U1B-PB6-Pad45)") (class "Default")
      (node (ref "U1") (pin "45") (pinfunction "PB6_45") (pintype "passive+no_connect"))
    )
    (net (code "77") (name "unconnected-(U1B-PB10-Pad22)") (class "Default")
      (node (ref "U1") (pin "22") (pinfunction "PB10_22") (pintype "passive+no_connect"))
    )
    (net (code "78") (name "unconnected-(U1B-PB11-Pad23)") (class "Default")
      (node (ref "U1") (pin "23") (pinfunction "PB11_23") (pintype "passive+no_connect"))
    )
    (net (code "79") (name "unconnected-(U1B-PB12-Pad24)") (class "Default")
      (node (ref "U1") (pin "24") (pinfunction "PB12_24") (pintype "passive+no_connect"))
    )
    (net (code "80") (name "unconnected-(U1B-PC7-Pad31)") (class "Default")
      (node (ref "U1") (pin "31") (pinfunction "PC7_31") (pintype "passive+no_connect"))
    )
    (net (code "81") (name "unconnected-(U1B-PD0-Pad38)") (class "Default")
      (node (ref "U1") (pin "38") (pinfunction "PD0_38") (pintype "passive+no_connect"))
    )
    (net (code "82") (name "unconnected-(U2-IND-Pad11)") (class "Default")
      (node (ref "U2") (pin "11") (pinfunction "IND_11") (pintype "passive+no_connect"))
    )
    (net (code "83") (name "unconnected-(U2-OUTD-Pad6)") (class "Default")
      (node (ref "U2") (pin "6") (pinfunction "OUTD_6") (pintype "passive+no_connect"))
    )
  )
)
